# ME6209.net
KiCad netlist of a schematic drawn in Altium Designer
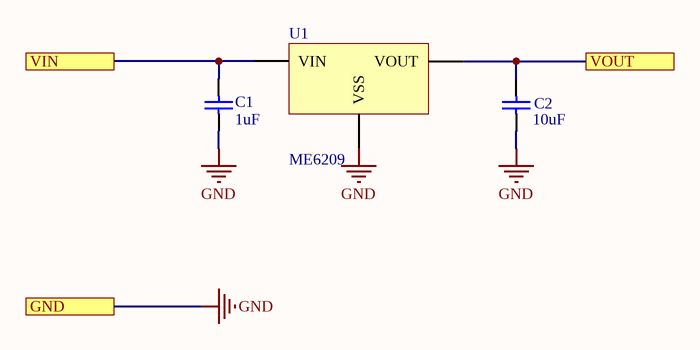
[diagram p0: ME6209.SchDoc]

(export (version "E")
  (design (tool "Eeschema 10.0.6"))
  (components
    (comp (ref "C1")
      (value "1uF")
      (footprint "LC-0603_C")
      (description "贴片电容")
      (libsource (lib "Miscellaneous Devices LC") (part "0603 1uF (105) 10% 50V"))
    )
    (comp (ref "C2")
      (value "10uF")
      (footprint "LC-0603_C")
      (description "贴片电容")
      (libsource (lib "Miscellaneous Devices LC") (part "0603 10uF (106) 10% 10V"))
    )
    (comp (ref "U1")
      (value "ME6209")
      (footprint "LC-SOT-23(SOT-23-3) - duplicate")
      (description "低压差线性稳压")
      (libsource (lib "user_Library") (part "ME6209"))
    )
  )
  (nets
    (net (code "1") (name "/VIN") (class "Default")
      (node (ref "C1") (pin "2") (pinfunction "2_2") (pintype "passive"))
      (node (ref "U1") (pin "3") (pinfunction "VIN_3") (pintype "passive"))
    )
    (net (code "2") (name "/VOUT") (class "Default")
      (node (ref "C2") (pin "2") (pinfunction "2_2") (pintype "passive"))
      (node (ref "U1") (pin "2") (pinfunction "VOUT_2") (pintype "passive"))
    )
    (net (code "3") (name "GND") (class "Default")
      (node (ref "C1") (pin "1") (pinfunction "1_1") (pintype "passive"))
      (node (ref "C2") (pin "1") (pinfunction "1_1") (pintype "passive"))
      (node (ref "U1") (pin "1") (pinfunction "VSS_1") (pintype "passive"))
    )
  )
)
